# main.net
KiCad netlist of a schematic drawn in Altium Designer
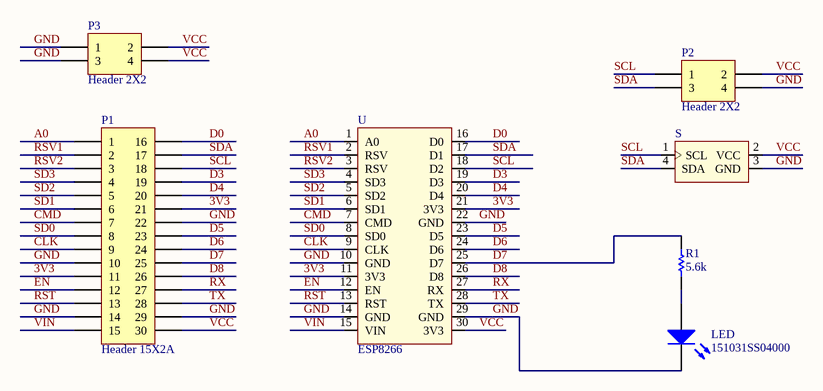
[diagram p0: main.SchDoc]

(export (version "E")
  (design (tool "Eeschema 10.0.6"))
  (components
    (comp (ref "LED")
      (value "151031SS04000")
      (footprint "Type 3mm")
      (description "THT LED round mono-color color lens, WL-TMRW, Super Red")
      (fields (field (name "MANUFACTURER") "Wuerth Elektronik"))
      (libsource (lib "Altium Content Vault") (part "CMP-1488-00005-1"))
    )
    (comp (ref "P1")
      (value "Header 15X2A")
      (footprint "HDR2X15_CEN")
      (description "Header, 15-Pin, Dual row")
      (fields (field (name "PUBLISHER") "Altium Limited"))
      (libsource (lib "Miscellaneous Connectors") (part "Header 15X2A"))
    )
    (comp (ref "P2")
      (value "Header 2X2")
      (footprint "HDR2X2")
      (description "Header, 2-Pin, Dual row")
      (fields (field (name "PUBLISHER") "Altium Limited"))
      (libsource (lib "Miscellaneous Connectors") (part "Header 2X2"))
    )
    (comp (ref "P3")
      (value "Header 2X2")
      (footprint "HDR2X2")
      (description "Header, 2-Pin, Dual row")
      (fields (field (name "PUBLISHER") "Altium Limited"))
      (libsource (lib "Miscellaneous Connectors") (part "Header 2X2"))
    )
    (comp (ref "R1")
      (value "5.6k")
      (footprint "RESC2013X70X40LL20T20")
      (description "Chip Resistor, 0 Ohm, +/- 5%, 125 mW, -55 to 155 degC, 0805 (2012 Metric), RoHS, Tape and Reel")
      (fields (field (name "PARTNUMBER") "ERJ-6GEY0R00V") (field (name "MANUFACTURER") "Basic Passives"))
      (libsource (lib "Altium Content Vault") (part "CMP-2001-00333-3"))
    )
    (comp (ref "S") (value "~") (footprint "To-5") (libsource (lib "IST") (part "TO-5")))
    (comp (ref "U")
      (value "ESP8266")
      (footprint "NodeMCU ESP8266")
      (libsource (lib "IST") (part "NodeMCU ESP8266"))
    )
  )
  (nets
    (net (code "1") (name "/3V3") (class "Default")
      (node (ref "P1") (pin "11") (pinfunction "11_11") (pintype "passive"))
      (node (ref "P1") (pin "21") (pinfunction "21_21") (pintype "passive"))
      (node (ref "U") (pin "11") (pinfunction "3V3_11") (pintype "passive"))
      (node (ref "U") (pin "21") (pinfunction "3V3_21") (pintype "passive"))
    )
    (net (code "2") (name "/A0") (class "Default")
      (node (ref "P1") (pin "1") (pinfunction "1_1") (pintype "passive"))
      (node (ref "U") (pin "1") (pinfunction "A0_1") (pintype "passive"))
    )
    (net (code "3") (name "/CLK") (class "Default")
      (node (ref "P1") (pin "9") (pinfunction "9_9") (pintype "passive"))
      (node (ref "U") (pin "9") (pinfunction "CLK_9") (pintype "passive"))
    )
    (net (code "4") (name "/CMD") (class "Default")
      (node (ref "P1") (pin "7") (pinfunction "7_7") (pintype "passive"))
      (node (ref "U") (pin "7") (pinfunction "CMD_7") (pintype "passive"))
    )
    (net (code "5") (name "/D0") (class "Default")
      (node (ref "P1") (pin "16") (pinfunction "16_16") (pintype "passive"))
      (node (ref "U") (pin "16") (pinfunction "D0_16") (pintype "passive"))
    )
    (net (code "6") (name "/D3") (class "Default")
      (node (ref "P1") (pin "19") (pinfunction "19_19") (pintype "passive"))
      (node (ref "U") (pin "19") (pinfunction "D3_19") (pintype "passive"))
    )
    (net (code "7") (name "/D4") (class "Default")
      (node (ref "P1") (pin "20") (pinfunction "20_20") (pintype "passive"))
      (node (ref "U") (pin "20") (pinfunction "D4_20") (pintype "passive"))
    )
    (net (code "8") (name "/D5") (class "Default")
      (node (ref "P1") (pin "23") (pinfunction "23_23") (pintype "passive"))
      (node (ref "U") (pin "23") (pinfunction "D5_23") (pintype "passive"))
    )
    (net (code "9") (name "/D6") (class "Default")
      (node (ref "P1") (pin "24") (pinfunction "24_24") (pintype "passive"))
      (node (ref "U") (pin "24") (pinfunction "D6_24") (pintype "passive"))
    )
    (net (code "10") (name "/D7") (class "Default")
      (node (ref "P1") (pin "25") (pinfunction "25_25") (pintype "passive"))
      (node (ref "R1") (pin "1") (pinfunction "1_1") (pintype "passive"))
      (node (ref "U") (pin "25") (pinfunction "D7_25") (pintype "passive"))
    )
    (net (code "11") (name "/D8") (class "Default")
      (node (ref "P1") (pin "26") (pinfunction "26_26") (pintype "passive"))
      (node (ref "U") (pin "26") (pinfunction "D8_26") (pintype "passive"))
    )
    (net (code "12") (name "/EN") (class "Default")
      (node (ref "P1") (pin "12") (pinfunction "12_12") (pintype "passive"))
      (node (ref "U") (pin "12") (pinfunction "EN_12") (pintype "passive"))
    )
    (net (code "13") (name "/GND") (class "Default")
      (node (ref "LED") (pin "1") (pinfunction "K_1") (pintype "passive"))
      (node (ref "P1") (pin "10") (pinfunction "10_10") (pintype "passive"))
      (node (ref "P1") (pin "14") (pinfunction "14_14") (pintype "passive"))
      (node (ref "P1") (pin "22") (pinfunction "22_22") (pintype "passive"))
      (node (ref "P1") (pin "29") (pinfunction "29_29") (pintype "passive"))
      (node (ref "P2") (pin "4") (pinfunction "4_4") (pintype "passive"))
      (node (ref "P3") (pin "1") (pinfunction "1_1") (pintype "passive"))
      (node (ref "P3") (pin "3") (pinfunction "3_3") (pintype "passive"))
      (node (ref "S") (pin "3") (pinfunction "GND_3") (pintype "passive"))
      (node (ref "U") (pin "10") (pinfunction "GND_10") (pintype "passive"))
      (node (ref "U") (pin "14") (pinfunction "GND_14") (pintype "passive"))
      (node (ref "U") (pin "22") (pinfunction "GND_22") (pintype "passive"))
      (node (ref "U") (pin "29") (pinfunction "GND_29") (pintype "passive"))
    )
    (net (code "14") (name "/RST") (class "Default")
      (node (ref "P1") (pin "13") (pinfunction "13_13") (pintype "passive"))
      (node (ref "U") (pin "13") (pinfunction "RST_13") (pintype "passive"))
    )
    (net (code "15") (name "/RSV1") (class "Default")
      (node (ref "P1") (pin "2") (pinfunction "2_2") (pintype "passive"))
      (node (ref "U") (pin "2") (pinfunction "RSV_2") (pintype "passive"))
    )
    (net (code "16") (name "/RSV2") (class "Default")
      (node (ref "P1") (pin "3") (pinfunction "3_3") (pintype "passive"))
      (node (ref "U") (pin "3") (pinfunction "RSV_3") (pintype "passive"))
    )
    (net (code "17") (name "/RX") (class "Default")
      (node (ref "P1") (pin "27") (pinfunction "27_27") (pintype "passive"))
      (node (ref "U") (pin "27") (pinfunction "RX_27") (pintype "passive"))
    )
    (net (code "18") (name "/SCL") (class "Default")
      (node (ref "P1") (pin "18") (pinfunction "18_18") (pintype "passive"))
      (node (ref "P2") (pin "1") (pinfunction "1_1") (pintype "passive"))
      (node (ref "S") (pin "1") (pinfunction "SCL_1") (pintype "passive"))
      (node (ref "U") (pin "18") (pinfunction "D2_18") (pintype "passive"))
    )
    (net (code "19") (name "/SD0") (class "Default")
      (node (ref "P1") (pin "8") (pinfunction "8_8") (pintype "passive"))
      (node (ref "U") (pin "8") (pinfunction "SD0_8") (pintype "passive"))
    )
    (net (code "20") (name "/SD1") (class "Default")
      (node (ref "P1") (pin "6") (pinfunction "6_6") (pintype "passive"))
      (node (ref "U") (pin "6") (pinfunction "SD1_6") (pintype "passive"))
    )
    (net (code "21") (name "/SD2") (class "Default")
      (node (ref "P1") (pin "5") (pinfunction "5_5") (pintype "passive"))
      (node (ref "U") (pin "5") (pinfunction "SD2_5") (pintype "passive"))
    )
    (net (code "22") (name "/SD3") (class "Default")
      (node (ref "P1") (pin "4") (pinfunction "4_4") (pintype "passive"))
      (node (ref "U") (pin "4") (pinfunction "SD3_4") (pintype "passive"))
    )
    (net (code "23") (name "/SDA") (class "Default")
      (node (ref "P1") (pin "17") (pinfunction "17_17") (pintype "passive"))
      (node (ref "P2") (pin "3") (pinfunction "3_3") (pintype "passive"))
      (node (ref "S") (pin "4") (pinfunction "SDA_4") (pintype "passive"))
      (node (ref "U") (pin "17") (pinfunction "D1_17") (pintype "passive"))
    )
    (net (code "24") (name "/TX") (class "Default")
      (node (ref "P1") (pin "28") (pinfunction "28_28") (pintype "passive"))
      (node (ref "U") (pin "28") (pinfunction "TX_28") (pintype "passive"))
    )
    (net (code "25") (name "/VCC") (class "Default")
      (node (ref "P1") (pin "30") (pinfunction "30_30") (pintype "passive"))
      (node (ref "P2") (pin "2") (pinfunction "2_2") (pintype "passive"))
      (node (ref "P3") (pin "2") (pinfunction "2_2") (pintype "passive"))
      (node (ref "P3") (pin "4") (pinfunction "4_4") (pintype "passive"))
      (node (ref "S") (pin "2") (pinfunction "VCC_2") (pintype "passive"))
      (node (ref "U") (pin "30") (pinfunction "3V3_30") (pintype "passive"))
    )
    (net (code "26") (name "/VIN") (class "Default")
      (node (ref "P1") (pin "15") (pinfunction "15_15") (pintype "passive"))
      (node (ref "U") (pin "15") (pinfunction "VIN_15") (pintype "passive"))
    )
    (net (code "27") (name "Net-(LED-A)") (class "Default")
      (node (ref "LED") (pin "2") (pinfunction "A_2") (pintype "passive"))
      (node (ref "R1") (pin "2") (pinfunction "2_2") (pintype "passive"))
    )
  )
)
